# FPGA.net
KiCad netlist of a schematic drawn in Altium Designer
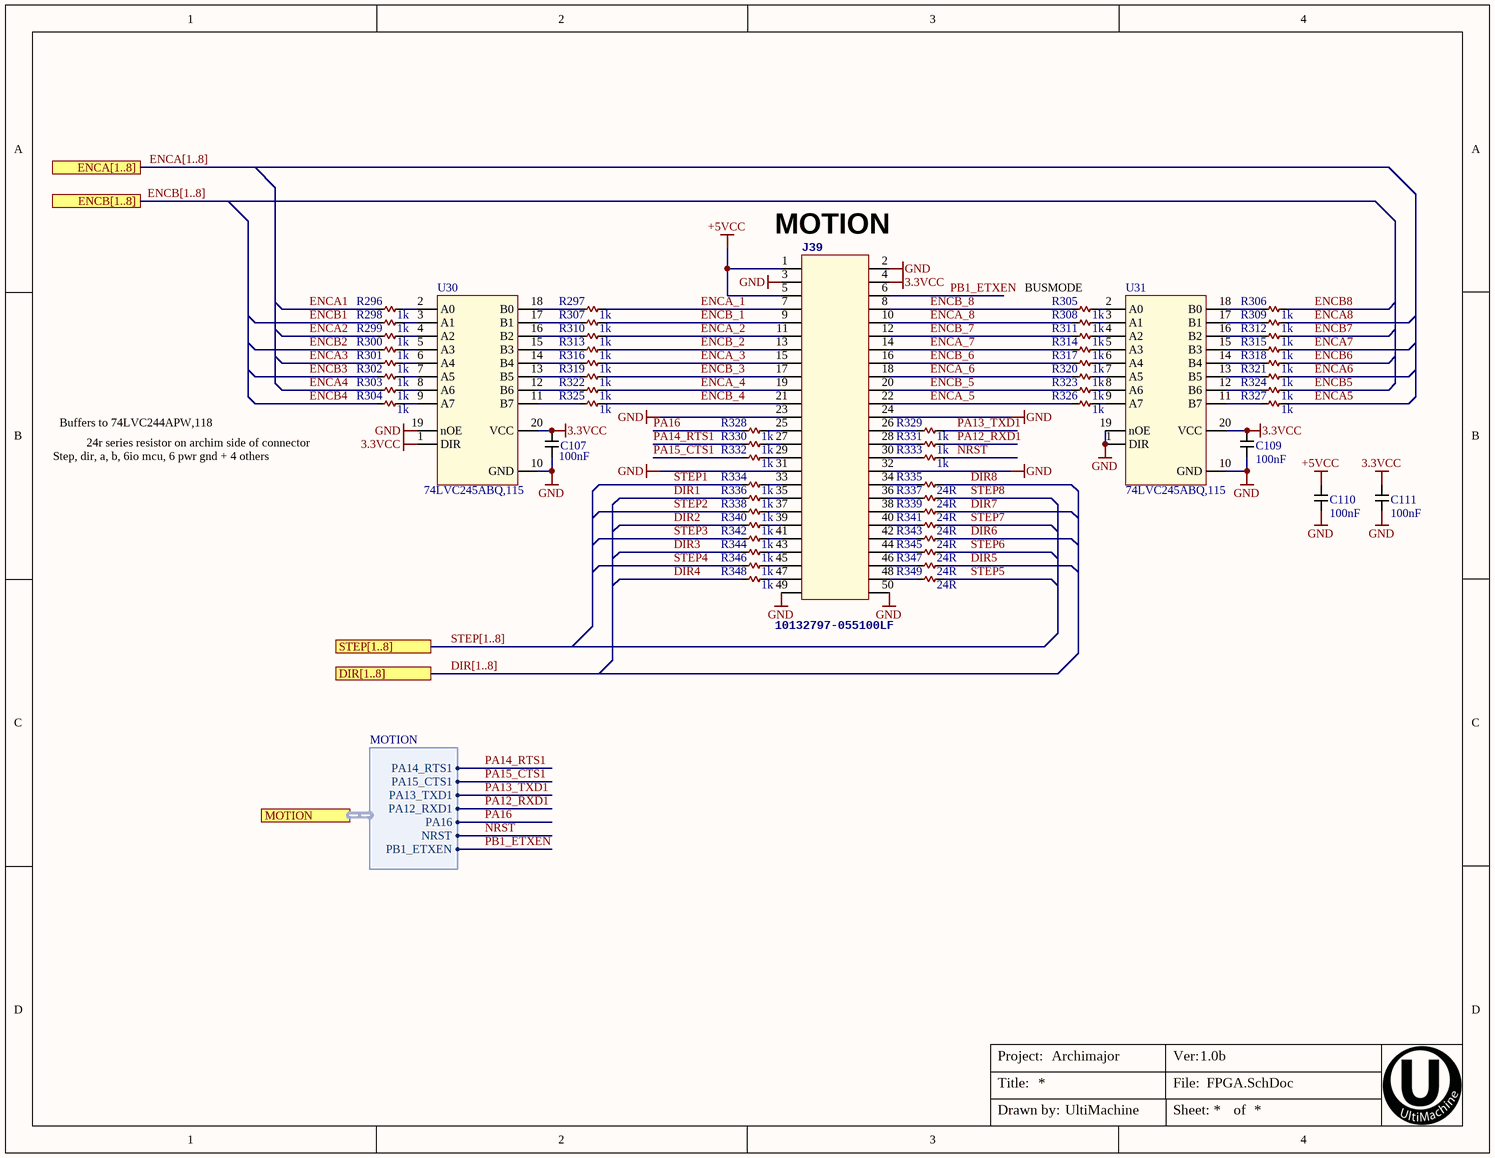
[diagram p0: FPGA.SchDoc]

(export (version "E")
  (design (tool "Eeschema 10.0.6"))
  (components
    (comp (ref "C107")
      (value "100nF")
      (footprint "C0201 Large Pads")
      (description "CAP CER 0.1UF 6.3V 10% X5R 0201")
      (fields (field (name "PART") ".1uF") (field (name "MANUFACTURER") "Samsung"))
      (libsource (lib "Capacitors") (part "100nF 6.3V X5R 0201"))
    )
    (comp (ref "C109")
      (value "100nF")
      (footprint "C0201 Large Pads")
      (description "CAP CER 0.1UF 6.3V 10% X5R 0201")
      (fields (field (name "PART") ".1uF") (field (name "MANUFACTURER") "Samsung"))
      (libsource (lib "Capacitors") (part "100nF 6.3V X5R 0201"))
    )
    (comp (ref "C110")
      (value "100nF")
      (footprint "C0201 Large Pads")
      (description "CAP CER 0.1UF 6.3V 10% X5R 0201")
      (fields (field (name "PART") ".1uF") (field (name "MANUFACTURER") "Samsung"))
      (libsource (lib "Capacitors") (part "100nF 6.3V X5R 0201"))
    )
    (comp (ref "C111")
      (value "100nF")
      (footprint "C0201 Large Pads")
      (description "CAP CER 0.1UF 6.3V 10% X5R 0201")
      (fields (field (name "PART") ".1uF") (field (name "MANUFACTURER") "Samsung"))
      (libsource (lib "Capacitors") (part "100nF 6.3V X5R 0201"))
    )
    (comp (ref "J39")
      (value "10132797-055100LF")
      (footprint "BTB 0.5mm 50pin-Female")
      (description "50 Position Connector Plug, Outer Shroud Contacts Surface Mount Gold")
      (libsource (lib "Connectors") (part "CONN 50 PIN 0.5mm FEMALE"))
    )
    (comp (ref "R296")
      (value "1k")
      (footprint "R0402")
      (description "RES 0402 1k 63mW 1%")
      (fields (field (name "MANUFACTURER") "Yageo") (field (name "PART") "1k 1% 0402"))
      (libsource (lib "Resistors") (part "1k 1% 0402"))
    )
    (comp (ref "R297")
      (value "1k")
      (footprint "R0402")
      (description "RES 0402 1k 63mW 1%")
      (fields (field (name "MANUFACTURER") "Yageo") (field (name "PART") "1k 1% 0402"))
      (libsource (lib "Resistors") (part "1k 1% 0402"))
    )
    (comp (ref "R298")
      (value "1k")
      (footprint "R0402")
      (description "RES 0402 1k 63mW 1%")
      (fields (field (name "MANUFACTURER") "Yageo") (field (name "PART") "1k 1% 0402"))
      (libsource (lib "Resistors") (part "1k 1% 0402"))
    )
    (comp (ref "R299")
      (value "1k")
      (footprint "R0402")
      (description "RES 0402 1k 63mW 1%")
      (fields (field (name "MANUFACTURER") "Yageo") (field (name "PART") "1k 1% 0402"))
      (libsource (lib "Resistors") (part "1k 1% 0402"))
    )
    (comp (ref "R300")
      (value "1k")
      (footprint "R0402")
      (description "RES 0402 1k 63mW 1%")
      (fields (field (name "MANUFACTURER") "Yageo") (field (name "PART") "1k 1% 0402"))
      (libsource (lib "Resistors") (part "1k 1% 0402"))
    )
    (comp (ref "R301")
      (value "1k")
      (footprint "R0402")
      (description "RES 0402 1k 63mW 1%")
      (fields (field (name "MANUFACTURER") "Yageo") (field (name "PART") "1k 1% 0402"))
      (libsource (lib "Resistors") (part "1k 1% 0402"))
    )
    (comp (ref "R302")
      (value "1k")
      (footprint "R0402")
      (description "RES 0402 1k 63mW 1%")
      (fields (field (name "MANUFACTURER") "Yageo") (field (name "PART") "1k 1% 0402"))
      (libsource (lib "Resistors") (part "1k 1% 0402"))
    )
    (comp (ref "R303")
      (value "1k")
      (footprint "R0402")
      (description "RES 0402 1k 63mW 1%")
      (fields (field (name "MANUFACTURER") "Yageo") (field (name "PART") "1k 1% 0402"))
      (libsource (lib "Resistors") (part "1k 1% 0402"))
    )
    (comp (ref "R304")
      (value "1k")
      (footprint "R0402")
      (description "RES 0402 1k 63mW 1%")
      (fields (field (name "MANUFACTURER") "Yageo") (field (name "PART") "1k 1% 0402"))
      (libsource (lib "Resistors") (part "1k 1% 0402"))
    )
    (comp (ref "R305")
      (value "1k")
      (footprint "R0402")
      (description "RES 0402 1k 63mW 1%")
      (fields (field (name "MANUFACTURER") "Yageo") (field (name "PART") "1k 1% 0402"))
      (libsource (lib "Resistors") (part "1k 1% 0402"))
    )
    (comp (ref "R306")
      (value "1k")
      (footprint "R0402")
      (description "RES 0402 1k 63mW 1%")
      (fields (field (name "MANUFACTURER") "Yageo") (field (name "PART") "1k 1% 0402"))
      (libsource (lib "Resistors") (part "1k 1% 0402"))
    )
    (comp (ref "R307")
      (value "1k")
      (footprint "R0402")
      (description "RES 0402 1k 63mW 1%")
      (fields (field (name "MANUFACTURER") "Yageo") (field (name "PART") "1k 1% 0402"))
      (libsource (lib "Resistors") (part "1k 1% 0402"))
    )
    (comp (ref "R308")
      (value "1k")
      (footprint "R0402")
      (description "RES 0402 1k 63mW 1%")
      (fields (field (name "MANUFACTURER") "Yageo") (field (name "PART") "1k 1% 0402"))
      (libsource (lib "Resistors") (part "1k 1% 0402"))
    )
    (comp (ref "R309")
      (value "1k")
      (footprint "R0402")
      (description "RES 0402 1k 63mW 1%")
      (fields (field (name "MANUFACTURER") "Yageo") (field (name "PART") "1k 1% 0402"))
      (libsource (lib "Resistors") (part "1k 1% 0402"))
    )
    (comp (ref "R310")
      (value "1k")
      (footprint "R0402")
      (description "RES 0402 1k 63mW 1%")
      (fields (field (name "MANUFACTURER") "Yageo") (field (name "PART") "1k 1% 0402"))
      (libsource (lib "Resistors") (part "1k 1% 0402"))
    )
    (comp (ref "R311")
      (value "1k")
      (footprint "R0402")
      (description "RES 0402 1k 63mW 1%")
      (fields (field (name "MANUFACTURER") "Yageo") (field (name "PART") "1k 1% 0402"))
      (libsource (lib "Resistors") (part "1k 1% 0402"))
    )
    (comp (ref "R312")
      (value "1k")
      (footprint "R0402")
      (description "RES 0402 1k 63mW 1%")
      (fields (field (name "MANUFACTURER") "Yageo") (field (name "PART") "1k 1% 0402"))
      (libsource (lib "Resistors") (part "1k 1% 0402"))
    )
    (comp (ref "R313")
      (value "1k")
      (footprint "R0402")
      (description "RES 0402 1k 63mW 1%")
      (fields (field (name "MANUFACTURER") "Yageo") (field (name "PART") "1k 1% 0402"))
      (libsource (lib "Resistors") (part "1k 1% 0402"))
    )
    (comp (ref "R314")
      (value "1k")
      (footprint "R0402")
      (description "RES 0402 1k 63mW 1%")
      (fields (field (name "MANUFACTURER") "Yageo") (field (name "PART") "1k 1% 0402"))
      (libsource (lib "Resistors") (part "1k 1% 0402"))
    )
    (comp (ref "R315")
      (value "1k")
      (footprint "R0402")
      (description "RES 0402 1k 63mW 1%")
      (fields (field (name "MANUFACTURER") "Yageo") (field (name "PART") "1k 1% 0402"))
      (libsource (lib "Resistors") (part "1k 1% 0402"))
    )
    (comp (ref "R316")
      (value "1k")
      (footprint "R0402")
      (description "RES 0402 1k 63mW 1%")
      (fields (field (name "MANUFACTURER") "Yageo") (field (name "PART") "1k 1% 0402"))
      (libsource (lib "Resistors") (part "1k 1% 0402"))
    )
    (comp (ref "R317")
      (value "1k")
      (footprint "R0402")
      (description "RES 0402 1k 63mW 1%")
      (fields (field (name "MANUFACTURER") "Yageo") (field (name "PART") "1k 1% 0402"))
      (libsource (lib "Resistors") (part "1k 1% 0402"))
    )
    (comp (ref "R318")
      (value "1k")
      (footprint "R0402")
      (description "RES 0402 1k 63mW 1%")
      (fields (field (name "MANUFACTURER") "Yageo") (field (name "PART") "1k 1% 0402"))
      (libsource (lib "Resistors") (part "1k 1% 0402"))
    )
    (comp (ref "R319")
      (value "1k")
      (footprint "R0402")
      (description "RES 0402 1k 63mW 1%")
      (fields (field (name "MANUFACTURER") "Yageo") (field (name "PART") "1k 1% 0402"))
      (libsource (lib "Resistors") (part "1k 1% 0402"))
    )
    (comp (ref "R320")
      (value "1k")
      (footprint "R0402")
      (description "RES 0402 1k 63mW 1%")
      (fields (field (name "MANUFACTURER") "Yageo") (field (name "PART") "1k 1% 0402"))
      (libsource (lib "Resistors") (part "1k 1% 0402"))
    )
    (comp (ref "R321")
      (value "1k")
      (footprint "R0402")
      (description "RES 0402 1k 63mW 1%")
      (fields (field (name "MANUFACTURER") "Yageo") (field (name "PART") "1k 1% 0402"))
      (libsource (lib "Resistors") (part "1k 1% 0402"))
    )
    (comp (ref "R322")
      (value "1k")
      (footprint "R0402")
      (description "RES 0402 1k 63mW 1%")
      (fields (field (name "MANUFACTURER") "Yageo") (field (name "PART") "1k 1% 0402"))
      (libsource (lib "Resistors") (part "1k 1% 0402"))
    )
    (comp (ref "R323")
      (value "1k")
      (footprint "R0402")
      (description "RES 0402 1k 63mW 1%")
      (fields (field (name "MANUFACTURER") "Yageo") (field (name "PART") "1k 1% 0402"))
      (libsource (lib "Resistors") (part "1k 1% 0402"))
    )
    (comp (ref "R324")
      (value "1k")
      (footprint "R0402")
      (description "RES 0402 1k 63mW 1%")
      (fields (field (name "MANUFACTURER") "Yageo") (field (name "PART") "1k 1% 0402"))
      (libsource (lib "Resistors") (part "1k 1% 0402"))
    )
    (comp (ref "R325")
      (value "1k")
      (footprint "R0402")
      (description "RES 0402 1k 63mW 1%")
      (fields (field (name "MANUFACTURER") "Yageo") (field (name "PART") "1k 1% 0402"))
      (libsource (lib "Resistors") (part "1k 1% 0402"))
    )
    (comp (ref "R326")
      (value "1k")
      (footprint "R0402")
      (description "RES 0402 1k 63mW 1%")
      (fields (field (name "MANUFACTURER") "Yageo") (field (name "PART") "1k 1% 0402"))
      (libsource (lib "Resistors") (part "1k 1% 0402"))
    )
    (comp (ref "R327")
      (value "1k")
      (footprint "R0402")
      (description "RES 0402 1k 63mW 1%")
      (fields (field (name "MANUFACTURER") "Yageo") (field (name "PART") "1k 1% 0402"))
      (libsource (lib "Resistors") (part "1k 1% 0402"))
    )
    (comp (ref "R328")
      (value "1k")
      (footprint "R0402")
      (description "RES 0402 1k 63mW 1%")
      (fields (field (name "MANUFACTURER") "Yageo") (field (name "PART") "1k 1% 0402"))
      (libsource (lib "Resistors") (part "1k 1% 0402"))
    )
    (comp (ref "R329")
      (value "1k")
      (footprint "R0402")
      (description "RES 0402 1k 63mW 1%")
      (fields (field (name "MANUFACTURER") "Yageo") (field (name "PART") "1k 1% 0402"))
      (libsource (lib "Resistors") (part "1k 1% 0402"))
    )
    (comp (ref "R330")
      (value "1k")
      (footprint "R0402")
      (description "RES 0402 1k 63mW 1%")
      (fields (field (name "MANUFACTURER") "Yageo") (field (name "PART") "1k 1% 0402"))
      (libsource (lib "Resistors") (part "1k 1% 0402"))
    )
    (comp (ref "R331")
      (value "1k")
      (footprint "R0402")
      (description "RES 0402 1k 63mW 1%")
      (fields (field (name "MANUFACTURER") "Yageo") (field (name "PART") "1k 1% 0402"))
      (libsource (lib "Resistors") (part "1k 1% 0402"))
    )
    (comp (ref "R332")
      (value "1k")
      (footprint "R0402")
      (description "RES 0402 1k 63mW 1%")
      (fields (field (name "MANUFACTURER") "Yageo") (field (name "PART") "1k 1% 0402"))
      (libsource (lib "Resistors") (part "1k 1% 0402"))
    )
    (comp (ref "R333")
      (value "1k")
      (footprint "R0402")
      (description "RES 0402 1k 63mW 1%")
      (fields (field (name "MANUFACTURER") "Yageo") (field (name "PART") "1k 1% 0402"))
      (libsource (lib "Resistors") (part "1k 1% 0402"))
    )
    (comp (ref "R334")
      (value "1k")
      (footprint "R0402")
      (description "RES 0402 1k 63mW 1%")
      (fields (field (name "MANUFACTURER") "Yageo") (field (name "PART") "1k 1% 0402"))
      (libsource (lib "Resistors") (part "1k 1% 0402"))
    )
    (comp (ref "R335")
      (value "24R")
      (footprint "R0402")
      (description "Res Thick Film 0402 24 Ohm 1% 0.063W")
      (fields (field (name "MANUFACTURER") "Yageo") (field (name "PART") "24R 1% 0402"))
      (libsource (lib "Resistors") (part "24R 1% 0402"))
    )
    (comp (ref "R336")
      (value "1k")
      (footprint "R0402")
      (description "RES 0402 1k 63mW 1%")
      (fields (field (name "MANUFACTURER") "Yageo") (field (name "PART") "1k 1% 0402"))
      (libsource (lib "Resistors") (part "1k 1% 0402"))
    )
    (comp (ref "R337")
      (value "24R")
      (footprint "R0402")
      (description "Res Thick Film 0402 24 Ohm 1% 0.063W")
      (fields (field (name "MANUFACTURER") "Yageo") (field (name "PART") "24R 1% 0402"))
      (libsource (lib "Resistors") (part "24R 1% 0402"))
    )
    (comp (ref "R338")
      (value "1k")
      (footprint "R0402")
      (description "RES 0402 1k 63mW 1%")
      (fields (field (name "MANUFACTURER") "Yageo") (field (name "PART") "1k 1% 0402"))
      (libsource (lib "Resistors") (part "1k 1% 0402"))
    )
    (comp (ref "R339")
      (value "24R")
      (footprint "R0402")
      (description "Res Thick Film 0402 24 Ohm 1% 0.063W")
      (fields (field (name "MANUFACTURER") "Yageo") (field (name "PART") "24R 1% 0402"))
      (libsource (lib "Resistors") (part "24R 1% 0402"))
    )
    (comp (ref "R340")
      (value "1k")
      (footprint "R0402")
      (description "RES 0402 1k 63mW 1%")
      (fields (field (name "MANUFACTURER") "Yageo") (field (name "PART") "1k 1% 0402"))
      (libsource (lib "Resistors") (part "1k 1% 0402"))
    )
    (comp (ref "R341")
      (value "24R")
      (footprint "R0402")
      (description "Res Thick Film 0402 24 Ohm 1% 0.063W")
      (fields (field (name "MANUFACTURER") "Yageo") (field (name "PART") "24R 1% 0402"))
      (libsource (lib "Resistors") (part "24R 1% 0402"))
    )
    (comp (ref "R342")
      (value "1k")
      (footprint "R0402")
      (description "RES 0402 1k 63mW 1%")
      (fields (field (name "MANUFACTURER") "Yageo") (field (name "PART") "1k 1% 0402"))
      (libsource (lib "Resistors") (part "1k 1% 0402"))
    )
    (comp (ref "R343")
      (value "24R")
      (footprint "R0402")
      (description "Res Thick Film 0402 24 Ohm 1% 0.063W")
      (fields (field (name "MANUFACTURER") "Yageo") (field (name "PART") "24R 1% 0402"))
      (libsource (lib "Resistors") (part "24R 1% 0402"))
    )
    (comp (ref "R344")
      (value "1k")
      (footprint "R0402")
      (description "RES 0402 1k 63mW 1%")
      (fields (field (name "MANUFACTURER") "Yageo") (field (name "PART") "1k 1% 0402"))
      (libsource (lib "Resistors") (part "1k 1% 0402"))
    )
    (comp (ref "R345")
      (value "24R")
      (footprint "R0402")
      (description "Res Thick Film 0402 24 Ohm 1% 0.063W")
      (fields (field (name "MANUFACTURER") "Yageo") (field (name "PART") "24R 1% 0402"))
      (libsource (lib "Resistors") (part "24R 1% 0402"))
    )
    (comp (ref "R346")
      (value "1k")
      (footprint "R0402")
      (description "RES 0402 1k 63mW 1%")
      (fields (field (name "MANUFACTURER") "Yageo") (field (name "PART") "1k 1% 0402"))
      (libsource (lib "Resistors") (part "1k 1% 0402"))
    )
    (comp (ref "R347")
      (value "24R")
      (footprint "R0402")
      (description "Res Thick Film 0402 24 Ohm 1% 0.063W")
      (fields (field (name "MANUFACTURER") "Yageo") (field (name "PART") "24R 1% 0402"))
      (libsource (lib "Resistors") (part "24R 1% 0402"))
    )
    (comp (ref "R348")
      (value "1k")
      (footprint "R0402")
      (description "RES 0402 1k 63mW 1%")
      (fields (field (name "MANUFACTURER") "Yageo") (field (name "PART") "1k 1% 0402"))
      (libsource (lib "Resistors") (part "1k 1% 0402"))
    )
    (comp (ref "R349")
      (value "24R")
      (footprint "R0402")
      (description "Res Thick Film 0402 24 Ohm 1% 0.063W")
      (fields (field (name "MANUFACTURER") "Yageo") (field (name "PART") "24R 1% 0402"))
      (libsource (lib "Resistors") (part "24R 1% 0402"))
    )
    (comp (ref "U30")
      (value "74LVC245ABQ,115")
      (footprint "QFN20-DHVQFN20-QFN50P250X450X100_HS-21L")
      (description "IC TXRX NON-INVERT 3.6V 20DHVQFN")
      (fields (field (name "TOLERANCE") "-NA-") (field (name "MANUFACTURER") "Nexperia"))
      (libsource (lib "ICs-Logic") (part "74LVC245ABQ,115"))
    )
    (comp (ref "U31")
      (value "74LVC245ABQ,115")
      (footprint "QFN20-DHVQFN20-QFN50P250X450X100_HS-21L")
      (description "IC TXRX NON-INVERT 3.6V 20DHVQFN")
      (fields (field (name "TOLERANCE") "-NA-") (field (name "MANUFACTURER") "Nexperia"))
      (libsource (lib "ICs-Logic") (part "74LVC245ABQ,115"))
    )
  )
  (nets
    (net (code "2") (name "+5VCC") (class "Default")
      (node (ref "C110") (pin "2") (pinfunction "2_2") (pintype "passive"))
      (node (ref "J39") (pin "1") (pinfunction "1_1") (pintype "power_in"))
      (node (ref "J39") (pin "5") (pinfunction "5_5") (pintype "power_in"))
    )
    (net (code "3") (name "/DIR1") (class "Default")
      (node (ref "R336") (pin "1") (pinfunction "1_1") (pintype "passive"))
    )
    (net (code "4") (name "/DIR2") (class "Default")
      (node (ref "R340") (pin "1") (pinfunction "1_1") (pintype "passive"))
    )
    (net (code "5") (name "/DIR3") (class "Default")
      (node (ref "R344") (pin "1") (pinfunction "1_1") (pintype "passive"))
    )
    (net (code "6") (name "/DIR4") (class "Default")
      (node (ref "R348") (pin "1") (pinfunction "1_1") (pintype "passive"))
    )
    (net (code "7") (name "/DIR5") (class "Default")
      (node (ref "R347") (pin "2") (pinfunction "2_2") (pintype "passive"))
    )
    (net (code "8") (name "/DIR6") (class "Default")
      (node (ref "R343") (pin "2") (pinfunction "2_2") (pintype "passive"))
    )
    (net (code "9") (name "/DIR7") (class "Default")
      (node (ref "R339") (pin "2") (pinfunction "2_2") (pintype "passive"))
    )
    (net (code "10") (name "/DIR8") (class "Default")
      (node (ref "R335") (pin "2") (pinfunction "2_2") (pintype "passive"))
    )
    (net (code "12") (name "/ENCA1") (class "Default")
      (node (ref "R296") (pin "1") (pinfunction "1_1") (pintype "passive"))
    )
    (net (code "13") (name "/ENCA2") (class "Default")
      (node (ref "R299") (pin "1") (pinfunction "1_1") (pintype "passive"))
    )
    (net (code "14") (name "/ENCA3") (class "Default")
      (node (ref "R301") (pin "1") (pinfunction "1_1") (pintype "passive"))
    )
    (net (code "15") (name "/ENCA4") (class "Default")
      (node (ref "R303") (pin "1") (pinfunction "1_1") (pintype "passive"))
    )
    (net (code "16") (name "/ENCA5") (class "Default")
      (node (ref "R327") (pin "2") (pinfunction "2_2") (pintype "passive"))
    )
    (net (code "17") (name "/ENCA6") (class "Default")
      (node (ref "R321") (pin "2") (pinfunction "2_2") (pintype "passive"))
    )
    (net (code "18") (name "/ENCA7") (class "Default")
      (node (ref "R315") (pin "2") (pinfunction "2_2") (pintype "passive"))
    )
    (net (code "19") (name "/ENCA8") (class "Default")
      (node (ref "R309") (pin "2") (pinfunction "2_2") (pintype "passive"))
    )
    (net (code "21") (name "/ENCA_1") (class "Default")
      (node (ref "J39") (pin "7") (pinfunction "7_7") (pintype "power_in"))
      (node (ref "R297") (pin "2") (pinfunction "2_2") (pintype "passive"))
    )
    (net (code "22") (name "/ENCA_2") (class "Default")
      (node (ref "J39") (pin "11") (pinfunction "11_11") (pintype "power_in"))
      (node (ref "R310") (pin "2") (pinfunction "2_2") (pintype "passive"))
    )
    (net (code "23") (name "/ENCA_3") (class "Default")
      (node (ref "J39") (pin "15") (pinfunction "15_15") (pintype "power_in"))
      (node (ref "R316") (pin "2") (pinfunction "2_2") (pintype "passive"))
    )
    (net (code "24") (name "/ENCA_4") (class "Default")
      (node (ref "J39") (pin "19") (pinfunction "19_19") (pintype "power_in"))
      (node (ref "R322") (pin "2") (pinfunction "2_2") (pintype "passive"))
    )
    (net (code "25") (name "/ENCA_5") (class "Default")
      (node (ref "J39") (pin "22") (pinfunction "22_22") (pintype "power_in"))
      (node (ref "R326") (pin "1") (pinfunction "1_1") (pintype "passive"))
    )
    (net (code "26") (name "/ENCA_6") (class "Default")
      (node (ref "J39") (pin "18") (pinfunction "18_18") (pintype "power_in"))
      (node (ref "R320") (pin "1") (pinfunction "1_1") (pintype "passive"))
    )
    (net (code "27") (name "/ENCA_7") (class "Default")
      (node (ref "J39") (pin "14") (pinfunction "14_14") (pintype "power_in"))
      (node (ref "R314") (pin "1") (pinfunction "1_1") (pintype "passive"))
    )
    (net (code "28") (name "/ENCA_8") (class "Default")
      (node (ref "J39") (pin "10") (pinfunction "10_10") (pintype "power_in"))
      (node (ref "R308") (pin "1") (pinfunction "1_1") (pintype "passive"))
    )
    (net (code "29") (name "/ENCB1") (class "Default")
      (node (ref "R298") (pin "1") (pinfunction "1_1") (pintype "passive"))
    )
    (net (code "30") (name "/ENCB2") (class "Default")
      (node (ref "R300") (pin "1") (pinfunction "1_1") (pintype "passive"))
    )
    (net (code "31") (name "/ENCB3") (class "Default")
      (node (ref "R302") (pin "1") (pinfunction "1_1") (pintype "passive"))
    )
    (net (code "32") (name "/ENCB4") (class "Default")
      (node (ref "R304") (pin "1") (pinfunction "1_1") (pintype "passive"))
    )
    (net (code "33") (name "/ENCB5") (class "Default")
      (node (ref "R324") (pin "2") (pinfunction "2_2") (pintype "passive"))
    )
    (net (code "34") (name "/ENCB6") (class "Default")
      (node (ref "R318") (pin "2") (pinfunction "2_2") (pintype "passive"))
    )
    (net (code "35") (name "/ENCB7") (class "Default")
      (node (ref "R312") (pin "2") (pinfunction "2_2") (pintype "passive"))
    )
    (net (code "36") (name "/ENCB8") (class "Default")
      (node (ref "R306") (pin "2") (pinfunction "2_2") (pintype "passive"))
    )
    (net (code "38") (name "/ENCB_1") (class "Default")
      (node (ref "J39") (pin "9") (pinfunction "9_9") (pintype "power_in"))
      (node (ref "R307") (pin "2") (pinfunction "2_2") (pintype "passive"))
    )
    (net (code "39") (name "/ENCB_2") (class "Default")
      (node (ref "J39") (pin "13") (pinfunction "13_13") (pintype "power_in"))
      (node (ref "R313") (pin "2") (pinfunction "2_2") (pintype "passive"))
    )
    (net (code "40") (name "/ENCB_3") (class "Default")
      (node (ref "J39") (pin "17") (pinfunction "17_17") (pintype "power_in"))
      (node (ref "R319") (pin "2") (pinfunction "2_2") (pintype "passive"))
    )
    (net (code "41") (name "/ENCB_4") (class "Default")
      (node (ref "J39") (pin "21") (pinfunction "21_21") (pintype "power_in"))
      (node (ref "R325") (pin "2") (pinfunction "2_2") (pintype "passive"))
    )
    (net (code "42") (name "/ENCB_5") (class "Default")
      (node (ref "J39") (pin "20") (pinfunction "20_20") (pintype "power_in"))
      (node (ref "R323") (pin "1") (pinfunction "1_1") (pintype "passive"))
    )
    (net (code "43") (name "/ENCB_6") (class "Default")
      (node (ref "J39") (pin "16") (pinfunction "16_16") (pintype "power_in"))
      (node (ref "R317") (pin "1") (pinfunction "1_1") (pintype "passive"))
    )
    (net (code "44") (name "/ENCB_7") (class "Default")
      (node (ref "J39") (pin "12") (pinfunction "12_12") (pintype "power_in"))
      (node (ref "R311") (pin "1") (pinfunction "1_1") (pintype "passive"))
    )
    (net (code "45") (name "/ENCB_8") (class "Default")
      (node (ref "J39") (pin "8") (pinfunction "8_8") (pintype "power_in"))
      (node (ref "R305") (pin "1") (pinfunction "1_1") (pintype "passive"))
    )
    (net (code "46") (name "/NRST") (class "Default")
      (node (ref "R333") (pin "2") (pinfunction "2_2") (pintype "passive"))
    )
    (net (code "47") (name "/PA12_RXD1") (class "Default")
      (node (ref "R331") (pin "2") (pinfunction "2_2") (pintype "passive"))
    )
    (net (code "48") (name "/PA13_TXD1") (class "Default")
      (node (ref "R329") (pin "2") (pinfunction "2_2") (pintype "passive"))
    )
    (net (code "49") (name "/PA14_RTS1") (class "Default")
      (node (ref "R330") (pin "1") (pinfunction "1_1") (pintype "passive"))
    )
    (net (code "50") (name "/PA15_CTS1") (class "Default")
      (node (ref "R332") (pin "1") (pinfunction "1_1") (pintype "passive"))
    )
    (net (code "51") (name "/PA16") (class "Default")
      (node (ref "R328") (pin "1") (pinfunction "1_1") (pintype "passive"))
    )
    (net (code "52") (name "/PB1_ETXEN") (class "Default")
      (node (ref "J39") (pin "6") (pinfunction "6_6") (pintype "power_in"))
    )
    (net (code "53") (name "/STEP1") (class "Default")
      (node (ref "R334") (pin "1") (pinfunction "1_1") (pintype "passive"))
    )
    (net (code "54") (name "/STEP2") (class "Default")
      (node (ref "R338") (pin "1") (pinfunction "1_1") (pintype "passive"))
    )
    (net (code "55") (name "/STEP3") (class "Default")
      (node (ref "R342") (pin "1") (pinfunction "1_1") (pintype "passive"))
    )
    (net (code "56") (name "/STEP4") (class "Default")
      (node (ref "R346") (pin "1") (pinfunction "1_1") (pintype "passive"))
    )
    (net (code "57") (name "/STEP5") (class "Default")
      (node (ref "R349") (pin "2") (pinfunction "2_2") (pintype "passive"))
    )
    (net (code "58") (name "/STEP6") (class "Default")
      (node (ref "R345") (pin "2") (pinfunction "2_2") (pintype "passive"))
    )
    (net (code "59") (name "/STEP7") (class "Default")
      (node (ref "R341") (pin "2") (pinfunction "2_2") (pintype "passive"))
    )
    (net (code "60") (name "/STEP8") (class "Default")
      (node (ref "R337") (pin "2") (pinfunction "2_2") (pintype "passive"))
    )
    (net (code "63") (name "3.3VCC") (class "Default")
      (node (ref "C107") (pin "2") (pinfunction "2_2") (pintype "passive"))
      (node (ref "C109") (pin "2") (pinfunction "2_2") (pintype "passive"))
      (node (ref "C111") (pin "2") (pinfunction "2_2") (pintype "passive"))
      (node (ref "J39") (pin "4") (pinfunction "4_4") (pintype "power_in"))
      (node (ref "U30") (pin "1") (pinfunction "DIR_1") (pintype "power_in"))
      (node (ref "U30") (pin "20") (pinfunction "VCC_20") (pintype "power_in"))
      (node (ref "U31") (pin "20") (pinfunction "VCC_20") (pintype "power_in"))
    )
    (net (code "64") (name "GND") (class "Default")
      (node (ref "C107") (pin "1") (pinfunction "1_1") (pintype "passive"))
      (node (ref "C109") (pin "1") (pinfunction "1_1") (pintype "passive"))
      (node (ref "C110") (pin "1") (pinfunction "1_1") (pintype "passive"))
      (node (ref "C111") (pin "1") (pinfunction "1_1") (pintype "passive"))
      (node (ref "J39") (pin "2") (pinfunction "2_2") (pintype "power_in"))
      (node (ref "J39") (pin "23") (pinfunction "23_23") (pintype "power_in"))
      (node (ref "J39") (pin "24") (pinfunction "24_24") (pintype "power_in"))
      (node (ref "J39") (pin "3") (pinfunction "3_3") (pintype "power_in"))
      (node (ref "J39") (pin "31") (pinfunction "31_31") (pintype "power_in"))
      (node (ref "J39") (pin "32") (pinfunction "32_32") (pintype "power_in"))
      (node (ref "J39") (pin "49") (pinfunction "49_49") (pintype "power_in"))
      (node (ref "J39") (pin "50") (pinfunction "50_50") (pintype "power_in"))
      (node (ref "U30") (pin "10") (pinfunction "GND_10") (pintype "power_in"))
      (node (ref "U30") (pin "19") (pinfunction "nOE_19") (pintype "power_in"))
      (node (ref "U31") (pin "1") (pinfunction "DIR_1") (pintype "power_in"))
      (node (ref "U31") (pin "10") (pinfunction "GND_10") (pintype "power_in"))
      (node (ref "U31") (pin "19") (pinfunction "nOE_19") (pintype "power_in"))
    )
    (net (code "65") (name "Net-(J39-Pad25)") (class "Default")
      (node (ref "J39") (pin "25") (pinfunction "25_25") (pintype "power_in"))
      (node (ref "R328") (pin "2") (pinfunction "2_2") (pintype "passive"))
    )
    (net (code "66") (name "Net-(J39-Pad26)") (class "Default")
      (node (ref "J39") (pin "26") (pinfunction "26_26") (pintype "power_in"))
      (node (ref "R329") (pin "1") (pinfunction "1_1") (pintype "passive"))
    )
    (net (code "67") (name "Net-(J39-Pad27)") (class "Default")
      (node (ref "J39") (pin "27") (pinfunction "27_27") (pintype "power_in"))
      (node (ref "R330") (pin "2") (pinfunction "2_2") (pintype "passive"))
    )
    (net (code "68") (name "Net-(J39-Pad28)") (class "Default")
      (node (ref "J39") (pin "28") (pinfunction "28_28") (pintype "power_in"))
      (node (ref "R331") (pin "1") (pinfunction "1_1") (pintype "passive"))
    )
    (net (code "69") (name "Net-(J39-Pad29)") (class "Default")
      (node (ref "J39") (pin "29") (pinfunction "29_29") (pintype "power_in"))
      (node (ref "R332") (pin "2") (pinfunction "2_2") (pintype "passive"))
    )
    (net (code "70") (name "Net-(J39-Pad30)") (class "Default")
      (node (ref "J39") (pin "30") (pinfunction "30_30") (pintype "power_in"))
      (node (ref "R333") (pin "1") (pinfunction "1_1") (pintype "passive"))
    )
    (net (code "71") (name "Net-(J39-Pad33)") (class "Default")
      (node (ref "J39") (pin "33") (pinfunction "33_33") (pintype "power_in"))
      (node (ref "R334") (pin "2") (pinfunction "2_2") (pintype "passive"))
    )
    (net (code "72") (name "Net-(J39-Pad34)") (class "Default")
      (node (ref "J39") (pin "34") (pinfunction "34_34") (pintype "power_in"))
      (node (ref "R335") (pin "1") (pinfunction "1_1") (pintype "passive"))
    )
    (net (code "73") (name "Net-(J39-Pad35)") (class "Default")
      (node (ref "J39") (pin "35") (pinfunction "35_35") (pintype "power_in"))
      (node (ref "R336") (pin "2") (pinfunction "2_2") (pintype "passive"))
    )
    (net (code "74") (name "Net-(J39-Pad36)") (class "Default")
      (node (ref "J39") (pin "36") (pinfunction "36_36") (pintype "power_in"))
      (node (ref "R337") (pin "1") (pinfunction "1_1") (pintype "passive"))
    )
    (net (code "75") (name "Net-(J39-Pad37)") (class "Default")
      (node (ref "J39") (pin "37") (pinfunction "37_37") (pintype "power_in"))
      (node (ref "R338") (pin "2") (pinfunction "2_2") (pintype "passive"))
    )
    (net (code "76") (name "Net-(J39-Pad38)") (class "Default")
      (node (ref "J39") (pin "38") (pinfunction "38_38") (pintype "power_in"))
      (node (ref "R339") (pin "1") (pinfunction "1_1") (pintype "passive"))
    )
    (net (code "77") (name "Net-(J39-Pad39)") (class "Default")
      (node (ref "J39") (pin "39") (pinfunction "39_39") (pintype "power_in"))
      (node (ref "R340") (pin "2") (pinfunction "2_2") (pintype "passive"))
    )
    (net (code "78") (name "Net-(J39-Pad40)") (class "Default")
      (node (ref "J39") (pin "40") (pinfunction "40_40") (pintype "power_in"))
      (node (ref "R341") (pin "1") (pinfunction "1_1") (pintype "passive"))
    )
    (net (code "79") (name "Net-(J39-Pad41)") (class "Default")
      (node (ref "J39") (pin "41") (pinfunction "41_41") (pintype "power_in"))
      (node (ref "R342") (pin "2") (pinfunction "2_2") (pintype "passive"))
    )
    (net (code "80") (name "Net-(J39-Pad42)") (class "Default")
      (node (ref "J39") (pin "42") (pinfunction "42_42") (pintype "power_in"))
      (node (ref "R343") (pin "1") (pinfunction "1_1") (pintype "passive"))
    )
    (net (code "81") (name "Net-(J39-Pad43)") (class "Default")
      (node (ref "J39") (pin "43") (pinfunction "43_43") (pintype "power_in"))
      (node (ref "R344") (pin "2") (pinfunction "2_2") (pintype "passive"))
    )
    (net (code "82") (name "Net-(J39-Pad44)") (class "Default")
      (node (ref "J39") (pin "44") (pinfunction "44_44") (pintype "power_in"))
      (node (ref "R345") (pin "1") (pinfunction "1_1") (pintype "passive"))
    )
    (net (code "83") (name "Net-(J39-Pad45)") (class "Default")
      (node (ref "J39") (pin "45") (pinfunction "45_45") (pintype "power_in"))
      (node (ref "R346") (pin "2") (pinfunction "2_2") (pintype "passive"))
    )
    (net (code "84") (name "Net-(J39-Pad46)") (class "Default")
      (node (ref "J39") (pin "46") (pinfunction "46_46") (pintype "power_in"))
      (node (ref "R347") (pin "1") (pinfunction "1_1") (pintype "passive"))
    )
    (net (code "85") (name "Net-(J39-Pad47)") (class "Default")
      (node (ref "J39") (pin "47") (pinfunction "47_47") (pintype "power_in"))
      (node (ref "R348") (pin "2") (pinfunction "2_2") (pintype "passive"))
    )
    (net (code "86") (name "Net-(J39-Pad48)") (class "Default")
      (node (ref "J39") (pin "48") (pinfunction "48_48") (pintype "power_in"))
      (node (ref "R349") (pin "1") (pinfunction "1_1") (pintype "passive"))
    )
    (net (code "87") (name "Net-(U30-A0)") (class "Default")
      (node (ref "R296") (pin "2") (pinfunction "2_2") (pintype "passive"))
      (node (ref "U30") (pin "2") (pinfunction "A0_2") (pintype "power_in"))
    )
    (net (code "88") (name "Net-(U30-A1)") (class "Default")
      (node (ref "R298") (pin "2") (pinfunction "2_2") (pintype "passive"))
      (node (ref "U30") (pin "3") (pinfunction "A1_3") (pintype "power_in"))
    )
    (net (code "89") (name "Net-(U30-A2)") (class "Default")
      (node (ref "R299") (pin "2") (pinfunction "2_2") (pintype "passive"))
      (node (ref "U30") (pin "4") (pinfunction "A2_4") (pintype "power_in"))
    )
    (net (code "90") (name "Net-(U30-A3)") (class "Default")
      (node (ref "R300") (pin "2") (pinfunction "2_2") (pintype "passive"))
      (node (ref "U30") (pin "5") (pinfunction "A3_5") (pintype "power_in"))
    )
    (net (code "91") (name "Net-(U30-A4)") (class "Default")
      (node (ref "R301") (pin "2") (pinfunction "2_2") (pintype "passive"))
      (node (ref "U30") (pin "6") (pinfunction "A4_6") (pintype "power_in"))
    )
    (net (code "92") (name "Net-(U30-A5)") (class "Default")
      (node (ref "R302") (pin "2") (pinfunction "2_2") (pintype "passive"))
      (node (ref "U30") (pin "7") (pinfunction "A5_7") (pintype "power_in"))
    )
    (net (code "93") (name "Net-(U30-A6)") (class "Default")
      (node (ref "R303") (pin "2") (pinfunction "2_2") (pintype "passive"))
      (node (ref "U30") (pin "8") (pinfunction "A6_8") (pintype "power_in"))
    )
    (net (code "94") (name "Net-(U30-A7)") (class "Default")
      (node (ref "R304") (pin "2") (pinfunction "2_2") (pintype "passive"))
      (node (ref "U30") (pin "9") (pinfunction "A7_9") (pintype "power_in"))
    )
    (net (code "95") (name "Net-(U30-B0)") (class "Default")
      (node (ref "R297") (pin "1") (pinfunction "1_1") (pintype "passive"))
      (node (ref "U30") (pin "18") (pinfunction "B0_18") (pintype "power_in"))
    )
    (net (code "96") (name "Net-(U30-B1)") (class "Default")
      (node (ref "R307") (pin "1") (pinfunction "1_1") (pintype "passive"))
      (node (ref "U30") (pin "17") (pinfunction "B1_17") (pintype "power_in"))
    )
    (net (code "97") (name "Net-(U30-B2)") (class "Default")
      (node (ref "R310") (pin "1") (pinfunction "1_1") (pintype "passive"))
      (node (ref "U30") (pin "16") (pinfunction "B2_16") (pintype "power_in"))
    )
    (net (code "98") (name "Net-(U30-B3)") (class "Default")
      (node (ref "R313") (pin "1") (pinfunction "1_1") (pintype "passive"))
      (node (ref "U30") (pin "15") (pinfunction "B3_15") (pintype "power_in"))
    )
    (net (code "99") (name "Net-(U30-B4)") (class "Default")
      (node (ref "R316") (pin "1") (pinfunction "1_1") (pintype "passive"))
      (node (ref "U30") (pin "14") (pinfunction "B4_14") (pintype "power_in"))
    )
    (net (code "100") (name "Net-(U30-B5)") (class "Default")
      (node (ref "R319") (pin "1") (pinfunction "1_1") (pintype "passive"))
      (node (ref "U30") (pin "13") (pinfunction "B5_13") (pintype "power_in"))
    )
    (net (code "101") (name "Net-(U30-B6)") (class "Default")
      (node (ref "R322") (pin "1") (pinfunction "1_1") (pintype "passive"))
      (node (ref "U30") (pin "12") (pinfunction "B6_12") (pintype "power_in"))
    )
    (net (code "102") (name "Net-(U30-B7)") (class "Default")
      (node (ref "R325") (pin "1") (pinfunction "1_1") (pintype "passive"))
      (node (ref "U30") (pin "11") (pinfunction "B7_11") (pintype "power_in"))
    )
    (net (code "103") (name "Net-(U31-A0)") (class "Default")
      (node (ref "R305") (pin "2") (pinfunction "2_2") (pintype "passive"))
      (node (ref "U31") (pin "2") (pinfunction "A0_2") (pintype "power_in"))
    )
    (net (code "104") (name "Net-(U31-A1)") (class "Default")
      (node (ref "R308") (pin "2") (pinfunction "2_2") (pintype "passive"))
      (node (ref "U31") (pin "3") (pinfunction "A1_3") (pintype "power_in"))
    )
    (net (code "105") (name "Net-(U31-A2)") (class "Default")
      (node (ref "R311") (pin "2") (pinfunction "2_2") (pintype "passive"))
      (node (ref "U31") (pin "4") (pinfunction "A2_4") (pintype "power_in"))
    )
    (net (code "106") (name "Net-(U31-A3)") (class "Default")
      (node (ref "R314") (pin "2") (pinfunction "2_2") (pintype "passive"))
      (node (ref "U31") (pin "5") (pinfunction "A3_5") (pintype "power_in"))
    )
    (net (code "107") (name "Net-(U31-A4)") (class "Default")
      (node (ref "R317") (pin "2") (pinfunction "2_2") (pintype "passive"))
      (node (ref "U31") (pin "6") (pinfunction "A4_6") (pintype "power_in"))
    )
    (net (code "108") (name "Net-(U31-A5)") (class "Default")
      (node (ref "R320") (pin "2") (pinfunction "2_2") (pintype "passive"))
      (node (ref "U31") (pin "7") (pinfunction "A5_7") (pintype "power_in"))
    )
    (net (code "109") (name "Net-(U31-A6)") (class "Default")
      (node (ref "R323") (pin "2") (pinfunction "2_2") (pintype "passive"))
      (node (ref "U31") (pin "8") (pinfunction "A6_8") (pintype "power_in"))
    )
    (net (code "110") (name "Net-(U31-A7)") (class "Default")
      (node (ref "R326") (pin "2") (pinfunction "2_2") (pintype "passive"))
      (node (ref "U31") (pin "9") (pinfunction "A7_9") (pintype "power_in"))
    )
    (net (code "111") (name "Net-(U31-B0)") (class "Default")
      (node (ref "R306") (pin "1") (pinfunction "1_1") (pintype "passive"))
      (node (ref "U31") (pin "18") (pinfunction "B0_18") (pintype "power_in"))
    )
    (net (code "112") (name "Net-(U31-B1)") (class "Default")
      (node (ref "R309") (pin "1") (pinfunction "1_1") (pintype "passive"))
      (node (ref "U31") (pin "17") (pinfunction "B1_17") (pintype "power_in"))
    )
    (net (code "113") (name "Net-(U31-B2)") (class "Default")
      (node (ref "R312") (pin "1") (pinfunction "1_1") (pintype "passive"))
      (node (ref "U31") (pin "16") (pinfunction "B2_16") (pintype "power_in"))
    )
    (net (code "114") (name "Net-(U31-B3)") (class "Default")
      (node (ref "R315") (pin "1") (pinfunction "1_1") (pintype "passive"))
      (node (ref "U31") (pin "15") (pinfunction "B3_15") (pintype "power_in"))
    )
    (net (code "115") (name "Net-(U31-B4)") (class "Default")
      (node (ref "R318") (pin "1") (pinfunction "1_1") (pintype "passive"))
      (node (ref "U31") (pin "14") (pinfunction "B4_14") (pintype "power_in"))
    )
    (net (code "116") (name "Net-(U31-B5)") (class "Default")
      (node (ref "R321") (pin "1") (pinfunction "1_1") (pintype "passive"))
      (node (ref "U31") (pin "13") (pinfunction "B5_13") (pintype "power_in"))
    )
    (net (code "117") (name "Net-(U31-B6)") (class "Default")
      (node (ref "R324") (pin "1") (pinfunction "1_1") (pintype "passive"))
      (node (ref "U31") (pin "12") (pinfunction "B6_12") (pintype "power_in"))
    )
    (net (code "118") (name "Net-(U31-B7)") (class "Default")
      (node (ref "R327") (pin "1") (pinfunction "1_1") (pintype "passive"))
      (node (ref "U31") (pin "11") (pinfunction "B7_11") (pintype "power_in"))
    )
    (net (code "119") (name "unconnected-(U30-NC-Pad23)") (class "Default")
      (node (ref "U30") (pin "23") (pinfunction "NC_23") (pintype "passive"))
    )
    (net (code "120") (name "unconnected-(U31-NC-Pad23)") (class "Default")
      (node (ref "U31") (pin "23") (pinfunction "NC_23") (pintype "passive"))
    )
  )
)
